# audio_spectrum.net
KiCad netlist of a schematic drawn in EAGLE
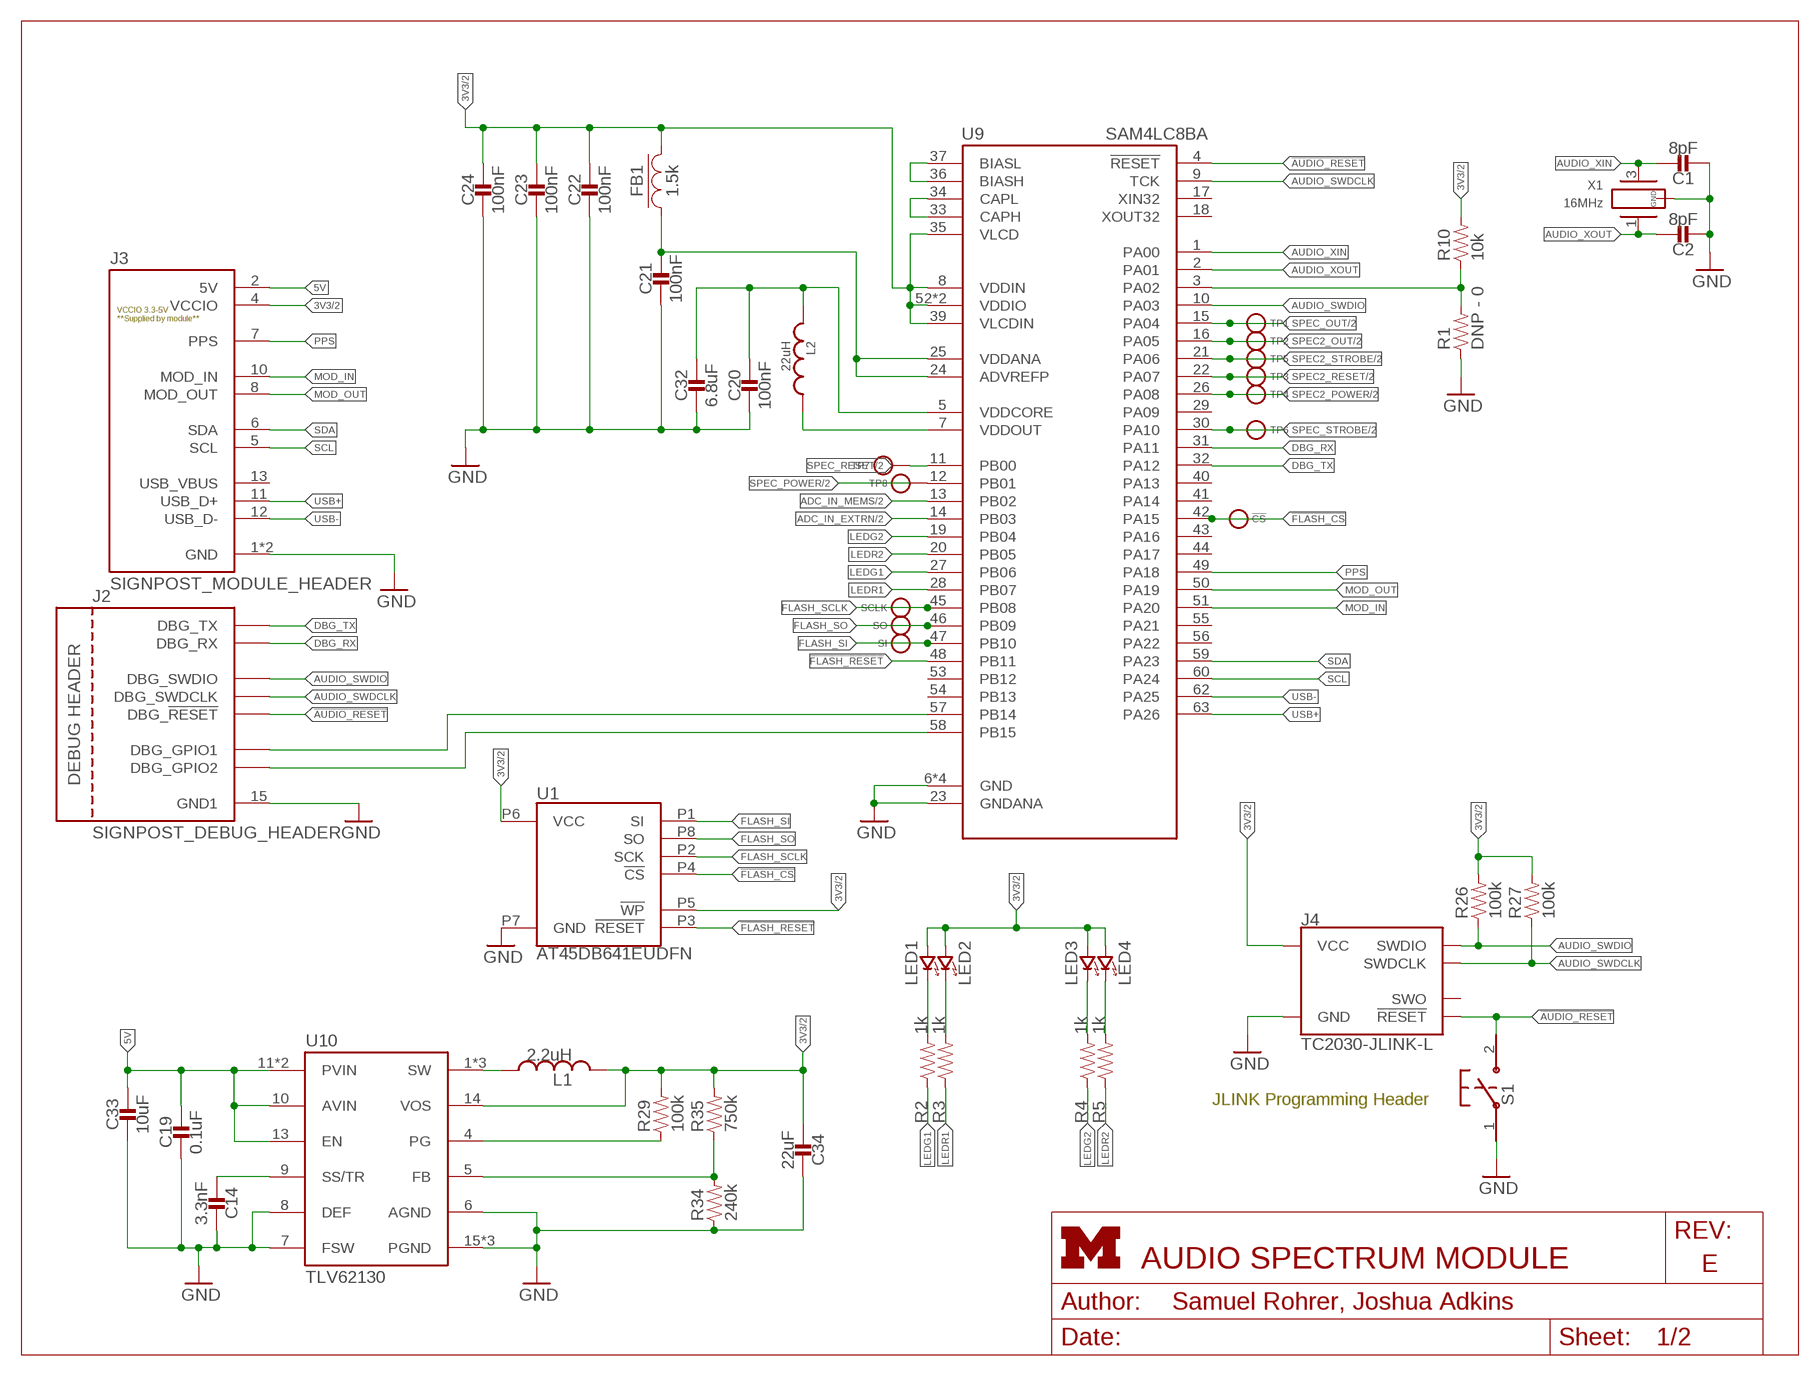
[diagram p0: schematic, sheet 1]
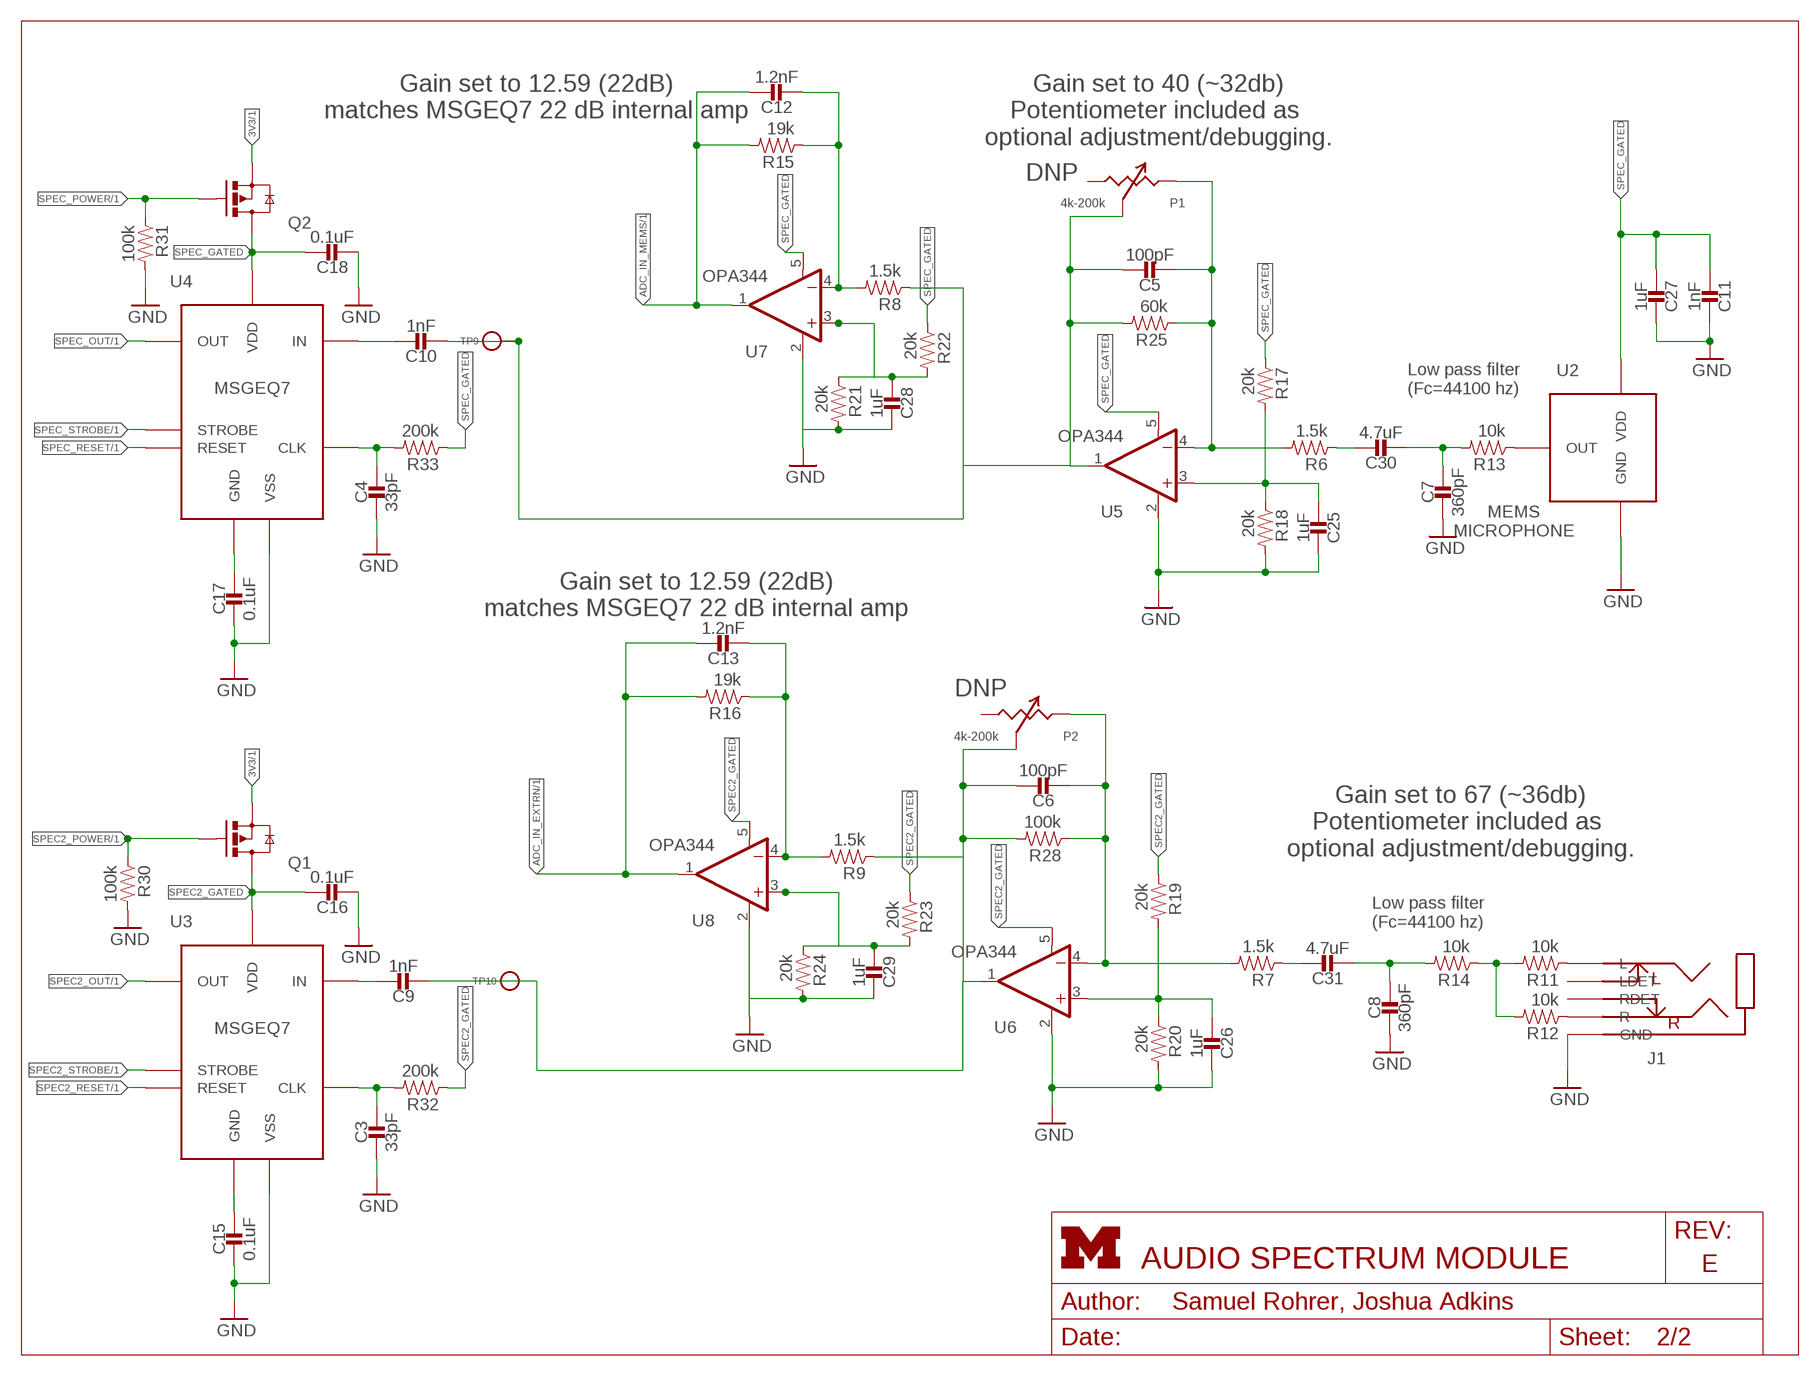
[diagram p1: schematic, sheet 2]

(export (version "E")
  (design (tool "Eeschema 10.0.6"))
  (components
    (comp (ref "!CS")
      (value "TEST_POINT_0.040IN")
      (footprint "eagle-import:TESTPOINT_0.040IN")
      (libsource (lib "eagle-import") (part "TEST_POINT_0.040IN"))
    )
    (comp (ref "C1")
      (value "8pF")
      (footprint "eagle-import:0402_CAP")
      (fields (field (name "MANUFACTURER") "Murata") (field (name "MPN") "GRM1555C1H8R0BA01D"))
      (libsource (lib "eagle-import") (part "CAPACITOR0402_CAP"))
    )
    (comp (ref "C2")
      (value "8pF")
      (footprint "eagle-import:0402_CAP")
      (fields (field (name "MANUFACTURER") "Murata") (field (name "MPN") "GRM1555C1H8R0BA01D"))
      (libsource (lib "eagle-import") (part "CAPACITOR0402_CAP"))
    )
    (comp (ref "C14")
      (value "3.3nF")
      (footprint "eagle-import:0603_CAP")
      (fields (field (name "MANUFACTURER") "Murata") (field (name "MPN") "GRM188R71H332KA01D"))
      (libsource (lib "eagle-import") (part "CAPACITOR0603_CAP"))
    )
    (comp (ref "C19")
      (value "0.1uF")
      (footprint "eagle-import:0603_CAP")
      (fields (field (name "MANUFACTURER") "Murata") (field (name "MPN") "GRM188R71C104KA01D"))
      (libsource (lib "eagle-import") (part "CAPACITOR0603_CAP"))
    )
    (comp (ref "C20")
      (value "100nF")
      (footprint "eagle-import:0402_CAP")
      (fields (field (name "MANUFACTURER") "Murata") (field (name "MPN") "GRM155R71A104JA01D"))
      (libsource (lib "eagle-import") (part "CAPACITOR0402_CAP"))
    )
    (comp (ref "C21")
      (value "100nF")
      (footprint "eagle-import:0603_CAP")
      (fields (field (name "MANUFACTURER") "Murata") (field (name "MPN") "GRM188R71C104KA01D"))
      (libsource (lib "eagle-import") (part "CAPACITOR0603_CAP"))
    )
    (comp (ref "C22")
      (value "100nF")
      (footprint "eagle-import:0603_CAP")
      (fields (field (name "MANUFACTURER") "Murata") (field (name "MPN") "GRM188R71C104KA01D"))
      (libsource (lib "eagle-import") (part "CAPACITOR0603_CAP"))
    )
    (comp (ref "C23")
      (value "100nF")
      (footprint "eagle-import:0603_CAP")
      (fields (field (name "MANUFACTURER") "Murata") (field (name "MPN") "GRM188R71C104KA01D"))
      (libsource (lib "eagle-import") (part "CAPACITOR0603_CAP"))
    )
    (comp (ref "C24")
      (value "100nF")
      (footprint "eagle-import:0603_CAP")
      (fields (field (name "MANUFACTURER") "Murata") (field (name "MPN") "GRM188R71C104KA01D"))
      (libsource (lib "eagle-import") (part "CAPACITOR0603_CAP"))
    )
    (comp (ref "C32")
      (value "6.8uF")
      (footprint "eagle-import:0603_CAP")
      (fields (field (name "MANUFACTURER") "TDk") (field (name "MPN") "C1608X5R1A685K080AC"))
      (libsource (lib "eagle-import") (part "CAPACITOR0603_CAP"))
    )
    (comp (ref "C33")
      (value "10uF")
      (footprint "eagle-import:0603_CAP")
      (fields (field (name "MANUFACTURER") "Murata") (field (name "MPN") "GRM188R60J106ME47J"))
      (libsource (lib "eagle-import") (part "CAPACITOR0603_CAP"))
    )
    (comp (ref "C34")
      (value "22uF")
      (footprint "eagle-import:0603_CAP")
      (fields (field (name "MANUFACTURER") "Murata") (field (name "MPN") "GRM186R60J226ME15D"))
      (libsource (lib "eagle-import") (part "CAPACITOR0603_CAP"))
    )
    (comp (ref "FB1")
      (value "1.5k")
      (footprint "eagle-import:0402_CAP")
      (fields (field (name "MANUFACTURER") "Murata") (field (name "MPN") "BLM18HE152SN1D"))
      (libsource (lib "eagle-import") (part "FERRITE_BEAD0402"))
    )
    (comp (ref "J2")
      (value "SIGNPOST_DEBUG_HEADER")
      (footprint "eagle-import:SIGNPOST_DEBUG_HEADER")
      (fields (field (name "MANUFACTURER") "Sullins Connector") (field (name "MPN") "PRPC004DFBN-RC"))
      (libsource (lib "eagle-import") (part "SIGNPOST_DEBUG_HEADER"))
    )
    (comp (ref "J3")
      (value "SIGNPOST_MODULE_HEADER")
      (footprint "eagle-import:SIGNPOST_MODULE_HEADER")
      (fields (field (name "MANUFACTURER") "Sullins Connector") (field (name "MPN") "SBH11-PBPC-D07-ST-BK"))
      (libsource (lib "eagle-import") (part "SIGNPOST_MODULE_HEADER"))
    )
    (comp (ref "J4")
      (value "TC2030-JLINK-L")
      (footprint "eagle-import:TC2030-IDC")
      (libsource (lib "eagle-import") (part "TC2030-JLINK-L"))
    )
    (comp (ref "L1")
      (value "2.2uH")
      (footprint "eagle-import:IHL-1212BZ-11")
      (fields (field (name "MANUFACTURER") "Vishay Dale") (field (name "MPN") "IHLP1212BZER2R2M11"))
      (libsource (lib "eagle-import") (part "INDUCTORIHL"))
    )
    (comp (ref "L2")
      (value "22uH")
      (footprint "eagle-import:1212")
      (fields
        (field (name "MANUFACTURER") "Murata")
        (field (name "MPN") "LQH3NPN220MJ0L")
        (field (name "MANUFACTURER_1") "Murata")
        (field (name "MPN_1") "LQH3NPN220MJ0L")
      )
      (libsource (lib "eagle-import") (part "LHQ3NP"))
    )
    (comp (ref "LED1")
      (value "LED0603")
      (footprint "eagle-import:LED-0603")
      (fields (field (name "MANUFACTURER") "Lite-On") (field (name "MPN") "LTST-C191KGKT"))
      (libsource (lib "eagle-import") (part "LED0603"))
    )
    (comp (ref "LED2")
      (value "LED0603")
      (footprint "eagle-import:LED-0603")
      (fields (field (name "MANUFACTURER") "Lite-On") (field (name "MPN") "LTST-C191KRKT"))
      (libsource (lib "eagle-import") (part "LED0603"))
    )
    (comp (ref "LED3")
      (value "LED0603")
      (footprint "eagle-import:LED-0603")
      (fields (field (name "MANUFACTURER") "Lite-On") (field (name "MPN") "LTST-C191KGKT"))
      (libsource (lib "eagle-import") (part "LED0603"))
    )
    (comp (ref "LED4")
      (value "LED0603")
      (footprint "eagle-import:LED-0603")
      (fields (field (name "MANUFACTURER") "Lite-On") (field (name "MPN") "LTST-C191KRKT"))
      (libsource (lib "eagle-import") (part "LED0603"))
    )
    (comp (ref "R1")
      (value "DNP - 0")
      (footprint "eagle-import:0603-RES")
      (fields (field (name "MANUFACTURER") "Samsung") (field (name "MPN") "RC1005F103CS"))
      (libsource (lib "eagle-import") (part "RESISTOR0603_RES"))
    )
    (comp (ref "R2")
      (value "1k")
      (footprint "eagle-import:0603-RES")
      (fields (field (name "MANUFACTURER") "Murata") (field (name "MPN") "ESR03EZPJ102"))
      (libsource (lib "eagle-import") (part "RESISTOR0603_RES"))
    )
    (comp (ref "R3")
      (value "1k")
      (footprint "eagle-import:0603-RES")
      (fields (field (name "MANUFACTURER") "Murata") (field (name "MPN") "ESR03EZPJ102"))
      (libsource (lib "eagle-import") (part "RESISTOR0603_RES"))
    )
    (comp (ref "R4")
      (value "1k")
      (footprint "eagle-import:0603-RES")
      (fields (field (name "MANUFACTURER") "Murata") (field (name "MPN") "ESR03EZPJ102"))
      (libsource (lib "eagle-import") (part "RESISTOR0603_RES"))
    )
    (comp (ref "R5")
      (value "1k")
      (footprint "eagle-import:0603-RES")
      (fields (field (name "MANUFACTURER") "Murata") (field (name "MPN") "ESR03EZPJ102"))
      (libsource (lib "eagle-import") (part "RESISTOR0603_RES"))
    )
    (comp (ref "R10")
      (value "10k")
      (footprint "eagle-import:0603-RES")
      (fields (field (name "MANUFACTURER") "Rohm") (field (name "MPN") "MCR03EZPFX1002"))
      (libsource (lib "eagle-import") (part "RESISTOR0603_RES"))
    )
    (comp (ref "R26")
      (value "100k")
      (footprint "eagle-import:0603-RES")
      (fields (field (name "MANUFACTURER") "Rohm") (field (name "MPN") "MCR03ERTJ104"))
      (libsource (lib "eagle-import") (part "RESISTOR0603_RES"))
    )
    (comp (ref "R27")
      (value "100k")
      (footprint "eagle-import:0603-RES")
      (fields (field (name "MANUFACTURER") "Rohm") (field (name "MPN") "MCR03ERTJ104"))
      (libsource (lib "eagle-import") (part "RESISTOR0603_RES"))
    )
    (comp (ref "R29")
      (value "100k")
      (footprint "eagle-import:0603-RES")
      (fields (field (name "MANUFACTURER") "Rohm") (field (name "MPN") "MCR03ERTJ104"))
      (libsource (lib "eagle-import") (part "RESISTOR0603_RES"))
    )
    (comp (ref "R34")
      (value "240k")
      (footprint "eagle-import:0603-RES")
      (fields (field (name "MANUFACTURER") "Rohm") (field (name "MPN") "RHM240KCFCT-ND"))
      (libsource (lib "eagle-import") (part "RESISTOR0603_RES"))
    )
    (comp (ref "R35")
      (value "750k")
      (footprint "eagle-import:0603-RES")
      (fields (field (name "MANUFACTURER") "Rohm") (field (name "MPN") "MCR03ERTF7503"))
      (libsource (lib "eagle-import") (part "RESISTOR0603_RES"))
    )
    (comp (ref "S1")
      (value "B3U-1000P")
      (footprint "eagle-import:B3U-1000P")
      (fields (field (name "MANUFACTURER") "Omron"))
      (libsource (lib "eagle-import") (part "B3U-1000P"))
    )
    (comp (ref "SCLK")
      (value "TEST_POINT_0.040IN")
      (footprint "eagle-import:TESTPOINT_0.040IN")
      (libsource (lib "eagle-import") (part "TEST_POINT_0.040IN"))
    )
    (comp (ref "SI")
      (value "TEST_POINT_0.040IN")
      (footprint "eagle-import:TESTPOINT_0.040IN")
      (libsource (lib "eagle-import") (part "TEST_POINT_0.040IN"))
    )
    (comp (ref "SO")
      (value "TEST_POINT_0.040IN")
      (footprint "eagle-import:TESTPOINT_0.040IN")
      (libsource (lib "eagle-import") (part "TEST_POINT_0.040IN"))
    )
    (comp (ref "TP1")
      (value "TEST_POINT_0.040IN")
      (footprint "eagle-import:TESTPOINT_0.040IN")
      (libsource (lib "eagle-import") (part "TEST_POINT_0.040IN"))
    )
    (comp (ref "TP2")
      (value "TEST_POINT_0.040IN")
      (footprint "eagle-import:TESTPOINT_0.040IN")
      (libsource (lib "eagle-import") (part "TEST_POINT_0.040IN"))
    )
    (comp (ref "TP3")
      (value "TEST_POINT_0.040IN")
      (footprint "eagle-import:TESTPOINT_0.040IN")
      (libsource (lib "eagle-import") (part "TEST_POINT_0.040IN"))
    )
    (comp (ref "TP4")
      (value "TEST_POINT_0.040IN")
      (footprint "eagle-import:TESTPOINT_0.040IN")
      (libsource (lib "eagle-import") (part "TEST_POINT_0.040IN"))
    )
    (comp (ref "TP5")
      (value "TEST_POINT_0.040IN")
      (footprint "eagle-import:TESTPOINT_0.040IN")
      (libsource (lib "eagle-import") (part "TEST_POINT_0.040IN"))
    )
    (comp (ref "TP6")
      (value "TEST_POINT_0.040IN")
      (footprint "eagle-import:TESTPOINT_0.040IN")
      (libsource (lib "eagle-import") (part "TEST_POINT_0.040IN"))
    )
    (comp (ref "TP7")
      (value "TEST_POINT_0.040IN")
      (footprint "eagle-import:TESTPOINT_0.040IN")
      (libsource (lib "eagle-import") (part "TEST_POINT_0.040IN"))
    )
    (comp (ref "TP8")
      (value "TEST_POINT_0.040IN")
      (footprint "eagle-import:TESTPOINT_0.040IN")
      (libsource (lib "eagle-import") (part "TEST_POINT_0.040IN"))
    )
    (comp (ref "U1")
      (value "AT45DB641EUDFN")
      (footprint "eagle-import:UDFN-8-5MMX6MM")
      (fields (field (name "MANUFACTURER") "Adesto") (field (name "MPN") "AT45DB641E-MHN-T"))
      (libsource (lib "eagle-import") (part "AT45DB641EUDFN"))
    )
    (comp (ref "U9")
      (value "SAM4LC8BA")
      (footprint "eagle-import:QFN-64-9MM")
      (fields (field (name "MANUFACTURER") "Microchip") (field (name "MPN") "ATSAM4LC8BA-MUR"))
      (libsource (lib "eagle-import") (part "SAM4LC8BA"))
    )
    (comp (ref "U10")
      (value "TLV62130")
      (footprint "eagle-import:TQFN-16_3MM")
      (fields (field (name "MANUFACTURER") "Texas Instruments") (field (name "MPN") "TLV62130RGTR"))
      (libsource (lib "eagle-import") (part "TLV62130"))
    )
    (comp (ref "X1")
      (value "16MHz")
      (footprint "eagle-import:FHXXX")
      (fields (field (name "MANUFACTURER") "Diodes Incorporated") (field (name "MPN") "FH1600015"))
      (libsource (lib "eagle-import") (part "FH1600015"))
    )
    (comp (ref "C3")
      (value "33pF")
      (footprint "eagle-import:0603_CAP")
      (fields (field (name "MANUFACTURER") "Murata") (field (name "MPN") "GRM1885C1H330JA01D"))
      (libsource (lib "eagle-import") (part "CAPACITOR0603_CAP"))
    )
    (comp (ref "C4")
      (value "33pF")
      (footprint "eagle-import:0603_CAP")
      (fields (field (name "MANUFACTURER") "Murata") (field (name "MPN") "GRM1885C1H330JA01D"))
      (libsource (lib "eagle-import") (part "CAPACITOR0603_CAP"))
    )
    (comp (ref "C5")
      (value "100pF")
      (footprint "eagle-import:0603_CAP")
      (fields (field (name "MANUFACTURER") "Murata") (field (name "MPN") "GRM1885C1H101JA01D"))
      (libsource (lib "eagle-import") (part "CAPACITOR0603_CAP"))
    )
    (comp (ref "C6")
      (value "100pF")
      (footprint "eagle-import:0603_CAP")
      (fields (field (name "MANUFACTURER") "Murata") (field (name "MPN") "GRM1885C1H101JA01D"))
      (libsource (lib "eagle-import") (part "CAPACITOR0603_CAP"))
    )
    (comp (ref "C7")
      (value "360pF")
      (footprint "eagle-import:0603_CAP")
      (fields (field (name "MANUFACTURER") "Murata") (field (name "MPN") "GRM1885C1H361JA01D"))
      (libsource (lib "eagle-import") (part "CAPACITOR0603_CAP"))
    )
    (comp (ref "C8")
      (value "360pF")
      (footprint "eagle-import:0603_CAP")
      (fields (field (name "MANUFACTURER") "Murata") (field (name "MPN") "GRM1885C1H361JA01D"))
      (libsource (lib "eagle-import") (part "CAPACITOR0603_CAP"))
    )
    (comp (ref "C9")
      (value "1nF")
      (footprint "eagle-import:0603_CAP")
      (fields (field (name "MANUFACTURER") "Murata") (field (name "MPN") "GRM188R71H102KA01D"))
      (libsource (lib "eagle-import") (part "CAPACITOR0603_CAP"))
    )
    (comp (ref "C10")
      (value "1nF")
      (footprint "eagle-import:0603_CAP")
      (fields (field (name "MANUFACTURER") "Murata") (field (name "MPN") "GRM188R71H102KA01D"))
      (libsource (lib "eagle-import") (part "CAPACITOR0603_CAP"))
    )
    (comp (ref "C11")
      (value "1nF")
      (footprint "eagle-import:0603_CAP")
      (fields (field (name "MANUFACTURER") "Murata") (field (name "MPN") "GRM188R71H102KA01D"))
      (libsource (lib "eagle-import") (part "CAPACITOR0603_CAP"))
    )
    (comp (ref "C12")
      (value "1.2nF")
      (footprint "eagle-import:0603_CAP")
      (fields (field (name "MANUFACTURER") "Murata") (field (name "MPN") "GCM1885C1H122JA16D"))
      (libsource (lib "eagle-import") (part "CAPACITOR0603_CAP"))
    )
    (comp (ref "C13")
      (value "1.2nF")
      (footprint "eagle-import:0603_CAP")
      (fields (field (name "MANUFACTURER") "Murata") (field (name "MPN") "GCM1885C1H122JA16D"))
      (libsource (lib "eagle-import") (part "CAPACITOR0603_CAP"))
    )
    (comp (ref "C15")
      (value "0.1uF")
      (footprint "eagle-import:0603_CAP")
      (fields (field (name "MANUFACTURER") "Murata") (field (name "MPN") "GRM188R71C104KA01D"))
      (libsource (lib "eagle-import") (part "CAPACITOR0603_CAP"))
    )
    (comp (ref "C16")
      (value "0.1uF")
      (footprint "eagle-import:0603_CAP")
      (fields (field (name "MANUFACTURER") "Murata") (field (name "MPN") "GRM188R71C104KA01D"))
      (libsource (lib "eagle-import") (part "CAPACITOR0603_CAP"))
    )
    (comp (ref "C17")
      (value "0.1uF")
      (footprint "eagle-import:0603_CAP")
      (fields (field (name "MANUFACTURER") "Murata") (field (name "MPN") "GRM188R71C104KA01D"))
      (libsource (lib "eagle-import") (part "CAPACITOR0603_CAP"))
    )
    (comp (ref "C18")
      (value "0.1uF")
      (footprint "eagle-import:0603_CAP")
      (fields (field (name "MANUFACTURER") "Murata") (field (name "MPN") "GRM188R71C104KA01D"))
      (libsource (lib "eagle-import") (part "CAPACITOR0603_CAP"))
    )
    (comp (ref "C25")
      (value "1uF")
      (footprint "eagle-import:0603_CAP")
      (fields (field (name "MANUFACTURER") "Murata") (field (name "MPN") "GRM188R61C105KA93D"))
      (libsource (lib "eagle-import") (part "CAPACITOR0603_CAP"))
    )
    (comp (ref "C26")
      (value "1uF")
      (footprint "eagle-import:0603_CAP")
      (fields (field (name "MANUFACTURER") "Murata") (field (name "MPN") "GRM188R61C105KA93D"))
      (libsource (lib "eagle-import") (part "CAPACITOR0603_CAP"))
    )
    (comp (ref "C27")
      (value "1uF")
      (footprint "eagle-import:0603_CAP")
      (fields (field (name "MANUFACTURER") "Murata") (field (name "MPN") "GRM188R61C105KA93D"))
      (libsource (lib "eagle-import") (part "CAPACITOR0603_CAP"))
    )
    (comp (ref "C28")
      (value "1uF")
      (footprint "eagle-import:0603_CAP")
      (fields (field (name "MANUFACTURER") "Murata") (field (name "MPN") "GRM188R61C105KA93D"))
      (libsource (lib "eagle-import") (part "CAPACITOR0603_CAP"))
    )
    (comp (ref "C29")
      (value "1uF")
      (footprint "eagle-import:0603_CAP")
      (fields (field (name "MANUFACTURER") "Murata") (field (name "MPN") "GRM188R61C105KA93D"))
      (libsource (lib "eagle-import") (part "CAPACITOR0603_CAP"))
    )
    (comp (ref "C30")
      (value "4.7uF")
      (footprint "eagle-import:0603_CAP")
      (fields (field (name "MANUFACTURER") "Murata") (field (name "MPN") "GRM188R60J475KE19D"))
      (libsource (lib "eagle-import") (part "CAPACITOR0603_CAP"))
    )
    (comp (ref "C31")
      (value "4.7uF")
      (footprint "eagle-import:0603_CAP")
      (fields (field (name "MANUFACTURER") "Murata") (field (name "MPN") "GRM188R60J475KE19D"))
      (libsource (lib "eagle-import") (part "CAPACITOR0603_CAP"))
    )
    (comp (ref "J1")
      (value "AUDIO-JACK-VERTICAL")
      (footprint "eagle-import:AUDIO-JACK-VERTICAL")
      (fields
        (field (name "MANUFACTURER") "Kycon")
        (field (name "MPN") "STX-3790-5N")
        (field (name "MANUFACTURER_1") "Kycon")
        (field (name "MPN_1") "STX-3790-5N")
      )
      (libsource (lib "eagle-import") (part "AUDIO-JACK-VERTICAL"))
    )
    (comp (ref "P1")
      (value "4k-200k")
      (footprint "eagle-import:TC33X-2")
      (libsource (lib "eagle-import") (part "POTTC33X"))
    )
    (comp (ref "P2")
      (value "4k-200k")
      (footprint "eagle-import:TC33X-2")
      (libsource (lib "eagle-import") (part "POTTC33X"))
    )
    (comp (ref "Q1")
      (value "NX3008PBK")
      (footprint "eagle-import:SOT23-3")
      (fields (field (name "MANUFACTURER") "Nexperia") (field (name "MPN") "NX3008PBK,215"))
      (libsource (lib "eagle-import") (part "NX3008PBK"))
    )
    (comp (ref "Q2")
      (value "NX3008PBK")
      (footprint "eagle-import:SOT23-3")
      (fields (field (name "MANUFACTURER") "Nexperia") (field (name "MPN") "NX3008PBK,215"))
      (libsource (lib "eagle-import") (part "NX3008PBK"))
    )
    (comp (ref "R6")
      (value "1.5k")
      (footprint "eagle-import:0603-RES")
      (fields (field (name "MANUFACTURER") "Rohm") (field (name "MPN") "MCR03ERTJ152 "))
      (libsource (lib "eagle-import") (part "RESISTOR0603_RES"))
    )
    (comp (ref "R7")
      (value "1.5k")
      (footprint "eagle-import:0603-RES")
      (fields (field (name "MANUFACTURER") "Rohm") (field (name "MPN") "MCR03ERTJ152 "))
      (libsource (lib "eagle-import") (part "RESISTOR0603_RES"))
    )
    (comp (ref "R8")
      (value "1.5k")
      (footprint "eagle-import:0603-RES")
      (fields (field (name "MANUFACTURER") "Rohm") (field (name "MPN") "MCR03ERTJ152"))
      (libsource (lib "eagle-import") (part "RESISTOR0603_RES"))
    )
    (comp (ref "R9")
      (value "1.5k")
      (footprint "eagle-import:0603-RES")
      (fields (field (name "MANUFACTURER") "Rohm") (field (name "MPN") "MCR03ERTJ152"))
      (libsource (lib "eagle-import") (part "RESISTOR0603_RES"))
    )
    (comp (ref "R11")
      (value "10k")
      (footprint "eagle-import:0603-RES")
      (fields (field (name "MANUFACTURER") "Rohm") (field (name "MPN") "MCR03EZPFX1002"))
      (libsource (lib "eagle-import") (part "RESISTOR0603_RES"))
    )
    (comp (ref "R12")
      (value "10k")
      (footprint "eagle-import:0603-RES")
      (fields (field (name "MANUFACTURER") "Rohm") (field (name "MPN") "MCR03EZPFX1002"))
      (libsource (lib "eagle-import") (part "RESISTOR0603_RES"))
    )
    (comp (ref "R13")
      (value "10k")
      (footprint "eagle-import:0603-RES")
      (fields (field (name "MANUFACTURER") "Rohm") (field (name "MPN") "MCR03EZPFX1002"))
      (libsource (lib "eagle-import") (part "RESISTOR0603_RES"))
    )
    (comp (ref "R14")
      (value "10k")
      (footprint "eagle-import:0603-RES")
      (fields (field (name "MANUFACTURER") "Rohm") (field (name "MPN") "MCR03EZPFX1002"))
      (libsource (lib "eagle-import") (part "RESISTOR0603_RES"))
    )
    (comp (ref "R15")
      (value "19k")
      (footprint "eagle-import:0603-RES")
      (fields (field (name "MANUFACTURER") "Rohm") (field (name "MPN") "MCR03ERTF1912"))
      (libsource (lib "eagle-import") (part "RESISTOR0603_RES"))
    )
    (comp (ref "R16")
      (value "19k")
      (footprint "eagle-import:0603-RES")
      (fields (field (name "MANUFACTURER") "Rohm") (field (name "MPN") "MCR03ERTF1912"))
      (libsource (lib "eagle-import") (part "RESISTOR0603_RES"))
    )
    (comp (ref "R17")
      (value "20k")
      (footprint "eagle-import:0603-RES")
      (fields (field (name "MANUFACTURER") "Rohm") (field (name "MPN") "MCR03ERTJ203"))
      (libsource (lib "eagle-import") (part "RESISTOR0603_RES"))
    )
    (comp (ref "R18")
      (value "20k")
      (footprint "eagle-import:0603-RES")
      (fields (field (name "MANUFACTURER") "Rohm") (field (name "MPN") "MCR03ERTJ203"))
      (libsource (lib "eagle-import") (part "RESISTOR0603_RES"))
    )
    (comp (ref "R19")
      (value "20k")
      (footprint "eagle-import:0603-RES")
      (fields (field (name "MANUFACTURER") "Rohm") (field (name "MPN") "MCR03ERTJ203"))
      (libsource (lib "eagle-import") (part "RESISTOR0603_RES"))
    )
    (comp (ref "R20")
      (value "20k")
      (footprint "eagle-import:0603-RES")
      (fields (field (name "MANUFACTURER") "Rohm") (field (name "MPN") "MCR03ERTJ203"))
      (libsource (lib "eagle-import") (part "RESISTOR0603_RES"))
    )
    (comp (ref "R21")
      (value "20k")
      (footprint "eagle-import:0603-RES")
      (fields (field (name "MANUFACTURER") "Rohm") (field (name "MPN") "MCR03ERTJ203"))
      (libsource (lib "eagle-import") (part "RESISTOR0603_RES"))
    )
    (comp (ref "R22")
      (value "20k")
      (footprint "eagle-import:0603-RES")
      (fields (field (name "MANUFACTURER") "Rohm") (field (name "MPN") "MCR03ERTJ203"))
      (libsource (lib "eagle-import") (part "RESISTOR0603_RES"))
    )
    (comp (ref "R23")
      (value "20k")
      (footprint "eagle-import:0603-RES")
      (fields (field (name "MANUFACTURER") "Rohm") (field (name "MPN") "MCR03ERTJ203"))
      (libsource (lib "eagle-import") (part "RESISTOR0603_RES"))
    )
    (comp (ref "R24")
      (value "20k")
      (footprint "eagle-import:0603-RES")
      (fields (field (name "MANUFACTURER") "Rohm") (field (name "MPN") "MCR03ERTJ203"))
      (libsource (lib "eagle-import") (part "RESISTOR0603_RES"))
    )
    (comp (ref "R25")
      (value "60k")
      (footprint "eagle-import:0603-RES")
      (fields (field (name "MANUFACTURER") "Rohm") (field (name "MPN") "MCR03ERTF6042"))
      (libsource (lib "eagle-import") (part "RESISTOR0603_RES"))
    )
    (comp (ref "R28")
      (value "100k")
      (footprint "eagle-import:0603-RES")
      (fields (field (name "MANUFACTURER") "Rohm") (field (name "MPN") "MCR03ERTJ104"))
      (libsource (lib "eagle-import") (part "RESISTOR0603_RES"))
    )
    (comp (ref "R30")
      (value "100k")
      (footprint "eagle-import:0603-RES")
      (fields (field (name "MANUFACTURER") "Rohm") (field (name "MPN") "MCR03ERTJ104"))
      (libsource (lib "eagle-import") (part "RESISTOR0603_RES"))
    )
    (comp (ref "R31")
      (value "100k")
      (footprint "eagle-import:0603-RES")
      (fields (field (name "MANUFACTURER") "Rohm") (field (name "MPN") "MCR03ERTJ104"))
      (libsource (lib "eagle-import") (part "RESISTOR0603_RES"))
    )
    (comp (ref "R32")
      (value "200k")
      (footprint "eagle-import:0603-RES")
      (fields (field (name "MANUFACTURER") "Rohm") (field (name "MPN") "MCR03ERTF2003"))
      (libsource (lib "eagle-import") (part "RESISTOR0603_RES"))
    )
    (comp (ref "R33")
      (value "200k")
      (footprint "eagle-import:0603-RES")
      (fields (field (name "MANUFACTURER") "Rohm") (field (name "MPN") "MCR03ERTF2003"))
      (libsource (lib "eagle-import") (part "RESISTOR0603_RES"))
    )
    (comp (ref "TP9")
      (value "TEST_POINT_0.040IN")
      (footprint "eagle-import:TESTPOINT_0.040IN")
      (libsource (lib "eagle-import") (part "TEST_POINT_0.040IN"))
    )
    (comp (ref "TP10")
      (value "TEST_POINT_0.040IN")
      (footprint "eagle-import:TESTPOINT_0.040IN")
      (libsource (lib "eagle-import") (part "TEST_POINT_0.040IN"))
    )
    (comp (ref "U2")
      (value "MP23AB02B")
      (footprint "eagle-import:MP23AB02B")
      (fields (field (name "MANUFACTURER") "STMicroelectronics") (field (name "MPN") "MP23AB02BTR"))
      (libsource (lib "eagle-import") (part "MP23AB02B"))
    )
    (comp (ref "U3")
      (value "MSGEQ7")
      (footprint "eagle-import:DIP-8")
      (fields (field (name "MANUFACTURER") "Sparkfun Electronics") (field (name "MPN") "COM-10468"))
      (libsource (lib "eagle-import") (part "MSGEQ7"))
    )
    (comp (ref "U4")
      (value "MSGEQ7")
      (footprint "eagle-import:DIP-8")
      (fields (field (name "MANUFACTURER") "Sparkfun Electronics") (field (name "MPN") "COM-10468"))
      (libsource (lib "eagle-import") (part "MSGEQ7"))
    )
    (comp (ref "U5")
      (value "OPA344")
      (footprint "eagle-import:SOT23-5")
      (fields
        (field (name "MANUFACTURER") "Texax Instruments")
        (field (name "MPN") "OPA344NA/250")
        (field (name "DIGIKEY") "OPA344NACT-ND")
      )
      (libsource (lib "eagle-import") (part "OPA344"))
    )
    (comp (ref "U6")
      (value "OPA344")
      (footprint "eagle-import:SOT23-5")
      (fields
        (field (name "MANUFACTURER") "Texax Instruments")
        (field (name "MPN") "OPA344NA/250")
        (field (name "DIGIKEY") "OPA344NACT-ND")
      )
      (libsource (lib "eagle-import") (part "OPA344"))
    )
    (comp (ref "U7")
      (value "OPA344")
      (footprint "eagle-import:SOT23-5")
      (fields
        (field (name "MANUFACTURER") "Texax Instruments")
        (field (name "MPN") "OPA344NA/250")
        (field (name "DIGIKEY") "OPA344NACT-ND")
      )
      (libsource (lib "eagle-import") (part "OPA344"))
    )
    (comp (ref "U8")
      (value "OPA344")
      (footprint "eagle-import:SOT23-5")
      (fields
        (field (name "MANUFACTURER") "Texax Instruments")
        (field (name "MPN") "OPA344NA/250")
        (field (name "DIGIKEY") "OPA344NACT-ND")
      )
      (libsource (lib "eagle-import") (part "OPA344"))
    )
  )
  (nets
    (net (code "1") (name "3V3") (class "Default")
      (node (ref "C22") (pin "1") (pinfunction "1_1") (pintype "bidirectional"))
      (node (ref "C23") (pin "1") (pinfunction "1_1") (pintype "bidirectional"))
      (node (ref "C24") (pin "1") (pinfunction "1_1") (pintype "bidirectional"))
      (node (ref "C34") (pin "2") (pinfunction "2_2") (pintype "bidirectional"))
      (node (ref "FB1") (pin "2") (pinfunction "P$2_2") (pintype "bidirectional"))
      (node (ref "J3") (pin "4") (pinfunction "VCCIO_4") (pintype "bidirectional"))
      (node (ref "J4") (pin "1") (pinfunction "VCC_1") (pintype "bidirectional"))
      (node (ref "L1") (pin "P$2") (pinfunction "2_P$2") (pintype "bidirectional"))
      (node (ref "LED1") (pin "A") (pinfunction "ANODE_A") (pintype "bidirectional"))
      (node (ref "LED2") (pin "A") (pinfunction "ANODE_A") (pintype "bidirectional"))
      (node (ref "LED3") (pin "A") (pinfunction "ANODE_A") (pintype "bidirectional"))
      (node (ref "LED4") (pin "A") (pinfunction "ANODE_A") (pintype "bidirectional"))
      (node (ref "Q1") (pin "2") (pinfunction "S_2") (pintype "passive"))
      (node (ref "Q2") (pin "2") (pinfunction "S_2") (pintype "passive"))
      (node (ref "R10") (pin "2") (pinfunction "2_2") (pintype "passive"))
      (node (ref "R26") (pin "2") (pinfunction "2_2") (pintype "passive"))
      (node (ref "R27") (pin "2") (pinfunction "2_2") (pintype "passive"))
      (node (ref "R29") (pin "2") (pinfunction "2_2") (pintype "passive"))
      (node (ref "R35") (pin "2") (pinfunction "2_2") (pintype "passive"))
      (node (ref "U1") (pin "P5") (pinfunction "~{WP}_P5") (pintype "bidirectional"))
      (node (ref "U1") (pin "P6") (pinfunction "VCC_P6") (pintype "bidirectional"))
      (node (ref "U10") (pin "14") (pinfunction "VOS_14") (pintype "bidirectional"))
      (node (ref "U9") (pin "35") (pinfunction "VLCD_35") (pintype "bidirectional"))
      (node (ref "U9") (pin "39") (pinfunction "VLCDIN_39") (pintype "power_in"))
      (node (ref "U9") (pin "52") (pinfunction "VDDIO_52") (pintype "power_in"))
      (node (ref "U9") (pin "61") (pinfunction "VDDIO_61") (pintype "power_in"))
      (node (ref "U9") (pin "8") (pinfunction "VDDIN_8") (pintype "power_in"))
    )
    (net (code "2") (name "5V") (class "Default")
      (node (ref "C19") (pin "1") (pinfunction "1_1") (pintype "bidirectional"))
      (node (ref "C33") (pin "1") (pinfunction "1_1") (pintype "bidirectional"))
      (node (ref "J3") (pin "2") (pinfunction "5V_2") (pintype "bidirectional"))
      (node (ref "U10") (pin "10") (pinfunction "AVIN_10") (pintype "bidirectional"))
      (node (ref "U10") (pin "11") (pinfunction "PVIN_11") (pintype "bidirectional"))
      (node (ref "U10") (pin "12") (pinfunction "PVIN_12") (pintype "bidirectional"))
      (node (ref "U10") (pin "13") (pinfunction "EN_13") (pintype "bidirectional"))
    )
    (net (code "3") (name "ADC_IN_EXTRN") (class "Default")
      (node (ref "C13") (pin "1") (pinfunction "1_1") (pintype "bidirectional"))
      (node (ref "R16") (pin "2") (pinfunction "2_2") (pintype "passive"))
      (node (ref "U8") (pin "1") (pinfunction "OUT_1") (pintype "output"))
      (node (ref "U9") (pin "14") (pinfunction "PB03_14") (pintype "bidirectional"))
    )
    (net (code "4") (name "ADC_IN_MEMS") (class "Default")
      (node (ref "C12") (pin "1") (pinfunction "1_1") (pintype "bidirectional"))
      (node (ref "R15") (pin "2") (pinfunction "2_2") (pintype "passive"))
      (node (ref "U7") (pin "1") (pinfunction "OUT_1") (pintype "output"))
      (node (ref "U9") (pin "13") (pinfunction "PB02_13") (pintype "bidirectional"))
    )
    (net (code "5") (name "AUDIO_SWDCLK") (class "Default")
      (node (ref "J2") (pin "21") (pinfunction "DBG_SWDCLK_21") (pintype "bidirectional"))
      (node (ref "J4") (pin "4") (pinfunction "SWDCLK_4") (pintype "bidirectional"))
      (node (ref "R27") (pin "1") (pinfunction "1_1") (pintype "passive"))
      (node (ref "U9") (pin "9") (pinfunction "TCK_9") (pintype "bidirectional"))
    )
    (net (code "6") (name "AUDIO_SWDIO") (class "Default")
      (node (ref "J2") (pin "22") (pinfunction "DBG_SWDIO_22") (pintype "bidirectional"))
      (node (ref "J4") (pin "2") (pinfunction "SWDIO_2") (pintype "bidirectional"))
      (node (ref "R26") (pin "1") (pinfunction "1_1") (pintype "passive"))
      (node (ref "U9") (pin "10") (pinfunction "PA03_10") (pintype "bidirectional"))
    )
    (net (code "7") (name "AUDIO_XIN") (class "Default")
      (node (ref "C1") (pin "1") (pinfunction "1_1") (pintype "bidirectional"))
      (node (ref "U9") (pin "1") (pinfunction "PA00_1") (pintype "bidirectional"))
      (node (ref "X1") (pin "3") (pinfunction "2_3") (pintype "bidirectional"))
    )
    (net (code "8") (name "AUDIO_XOUT") (class "Default")
      (node (ref "C2") (pin "1") (pinfunction "1_1") (pintype "bidirectional"))
      (node (ref "U9") (pin "2") (pinfunction "PA01_2") (pintype "bidirectional"))
      (node (ref "X1") (pin "1") (pinfunction "1_1") (pintype "bidirectional"))
    )
    (net (code "9") (name "DBG_RX") (class "Default")
      (node (ref "J2") (pin "18") (pinfunction "DBG_RX_18") (pintype "bidirectional"))
      (node (ref "U9") (pin "31") (pinfunction "PA11_31") (pintype "bidirectional"))
    )
    (net (code "10") (name "DBG_TX") (class "Default")
      (node (ref "J2") (pin "17") (pinfunction "DBG_TX_17") (pintype "bidirectional"))
      (node (ref "U9") (pin "32") (pinfunction "PA12_32") (pintype "bidirectional"))
    )
    (net (code "11") (name "FLASH_SCLK") (class "Default")
      (node (ref "SCLK") (pin "TESTPOINT") (pinfunction "TESTPOINT_TESTPOINT") (pintype "bidirectional"))
      (node (ref "U1") (pin "P2") (pinfunction "SCK_P2") (pintype "bidirectional"))
      (node (ref "U9") (pin "45") (pinfunction "PB08_45") (pintype "bidirectional"))
    )
    (net (code "12") (name "FLASH_SI") (class "Default")
      (node (ref "SI") (pin "TESTPOINT") (pinfunction "TESTPOINT_TESTPOINT") (pintype "bidirectional"))
      (node (ref "U1") (pin "P1") (pinfunction "SI_P1") (pintype "bidirectional"))
      (node (ref "U9") (pin "47") (pinfunction "PB10_47") (pintype "bidirectional"))
    )
    (net (code "13") (name "FLASH_SO") (class "Default")
      (node (ref "SO") (pin "TESTPOINT") (pinfunction "TESTPOINT_TESTPOINT") (pintype "bidirectional"))
      (node (ref "U1") (pin "P8") (pinfunction "SO_P8") (pintype "bidirectional"))
      (node (ref "U9") (pin "46") (pinfunction "PB09_46") (pintype "bidirectional"))
    )
    (net (code "14") (name "GND") (class "Default")
      (node (ref "C1") (pin "2") (pinfunction "2_2") (pintype "bidirectional"))
      (node (ref "C11") (pin "1") (pinfunction "1_1") (pintype "bidirectional"))
      (node (ref "C14") (pin "1") (pinfunction "1_1") (pintype "bidirectional"))
      (node (ref "C15") (pin "2") (pinfunction "2_2") (pintype "bidirectional"))
      (node (ref "C16") (pin "2") (pinfunction "2_2") (pintype "bidirectional"))
      (node (ref "C17") (pin "2") (pinfunction "2_2") (pintype "bidirectional"))
      (node (ref "C18") (pin "2") (pinfunction "2_2") (pintype "bidirectional"))
      (node (ref "C19") (pin "2") (pinfunction "2_2") (pintype "bidirectional"))
      (node (ref "C2") (pin "2") (pinfunction "2_2") (pintype "bidirectional"))
      (node (ref "C20") (pin "2") (pinfunction "2_2") (pintype "bidirectional"))
      (node (ref "C21") (pin "2") (pinfunction "2_2") (pintype "bidirectional"))
      (node (ref "C22") (pin "2") (pinfunction "2_2") (pintype "bidirectional"))
      (node (ref "C23") (pin "2") (pinfunction "2_2") (pintype "bidirectional"))
      (node (ref "C24") (pin "2") (pinfunction "2_2") (pintype "bidirectional"))
      (node (ref "C25") (pin "1") (pinfunction "1_1") (pintype "bidirectional"))
      (node (ref "C26") (pin "1") (pinfunction "1_1") (pintype "bidirectional"))
      (node (ref "C27") (pin "1") (pinfunction "1_1") (pintype "bidirectional"))
      (node (ref "C28") (pin "1") (pinfunction "1_1") (pintype "bidirectional"))
      (node (ref "C29") (pin "1") (pinfunction "1_1") (pintype "bidirectional"))
      (node (ref "C3") (pin "2") (pinfunction "2_2") (pintype "bidirectional"))
      (node (ref "C32") (pin "2") (pinfunction "2_2") (pintype "bidirectional"))
      (node (ref "C33") (pin "2") (pinfunction "2_2") (pintype "bidirectional"))
      (node (ref "C34") (pin "1") (pinfunction "1_1") (pintype "bidirectional"))
      (node (ref "C4") (pin "2") (pinfunction "2_2") (pintype "bidirectional"))
      (node (ref "C7") (pin "2") (pinfunction "2_2") (pintype "bidirectional"))
      (node (ref "C8") (pin "2") (pinfunction "2_2") (pintype "bidirectional"))
      (node (ref "J1") (pin "5") (pinfunction "GND_5") (pintype "bidirectional"))
      (node (ref "J2") (pin "15") (pinfunction "GND1_15") (pintype "bidirectional"))
      (node (ref "J3") (pin "1") (pinfunction "GND_1") (pintype "bidirectional"))
      (node (ref "J3") (pin "14") (pinfunction "GND_14") (pintype "bidirectional"))
      (node (ref "J4") (pin "5") (pinfunction "GND_5") (pintype "bidirectional"))
      (node (ref "R1") (pin "1") (pinfunction "1_1") (pintype "passive"))
      (node (ref "R18") (pin "2") (pinfunction "2_2") (pintype "passive"))
      (node (ref "R20") (pin "2") (pinfunction "2_2") (pintype "passive"))
      (node (ref "R21") (pin "2") (pinfunction "2_2") (pintype "passive"))
      (node (ref "R24") (pin "2") (pinfunction "2_2") (pintype "passive"))
      (node (ref "R30") (pin "2") (pinfunction "2_2") (pintype "passive"))
      (node (ref "R31") (pin "2") (pinfunction "2_2") (pintype "passive"))
      (node (ref "R34") (pin "1") (pinfunction "1_1") (pintype "passive"))
      (node (ref "S1") (pin "1") (pinfunction "P$1_1") (pintype "passive"))
      (node (ref "U1") (pin "P7") (pinfunction "GND_P7") (pintype "bidirectional"))
      (node (ref "U10") (pin "15") (pinfunction "PGND_15") (pintype "bidirectional"))
      (node (ref "U10") (pin "16") (pinfunction "PGND_16") (pintype "bidirectional"))
      (node (ref "U10") (pin "6") (pinfunction "AGND_6") (pintype "bidirectional"))
      (node (ref "U10") (pin "7") (pinfunction "FSW_7") (pintype "bidirectional"))
      (node (ref "U10") (pin "8") (pinfunction "DEF_8") (pintype "bidirectional"))
      (node (ref "U10") (pin "GND") (pinfunction "PGND_GND") (pintype "bidirectional"))
      (node (ref "U2") (pin "3") (pinfunction "GND_3") (pintype "bidirectional"))
      (node (ref "U3") (pin "2") (pinfunction "VSS_2") (pintype "bidirectional"))
      (node (ref "U4") (pin "2") (pinfunction "VSS_2") (pintype "bidirectional"))
      (node (ref "U5") (pin "2") (pinfunction "V-_2") (pintype "power_in"))
      (node (ref "U6") (pin "2") (pinfunction "V-_2") (pintype "power_in"))
      (node (ref "U7") (pin "2") (pinfunction "V-_2") (pintype "power_in"))
      (node (ref "U8") (pin "2") (pinfunction "V-_2") (pintype "power_in"))
      (node (ref "U9") (pin "23") (pinfunction "GNDANA_23") (pintype "power_in"))
      (node (ref "U9") (pin "38") (pinfunction "GND_38") (pintype "power_in"))
      (node (ref "U9") (pin "6") (pinfunction "GND_6") (pintype "power_in"))
      (node (ref "U9") (pin "64") (pinfunction "GND_64") (pintype "power_in"))
      (node (ref "U9") (pin "GND") (pinfunction "GND_GND") (pintype "power_in"))
      (node (ref "X1") (pin "2") (pinfunction "GND_2") (pintype "bidirectional"))
      (node (ref "X1") (pin "4") (pinfunction "GND_4") (pintype "bidirectional"))
    )
    (net (code "15") (name "LEDG1") (class "Default")
      (node (ref "R2") (pin "1") (pinfunction "1_1") (pintype "passive"))
      (node (ref "U9") (pin "27") (pinfunction "PB06_27") (pintype "bidirectional"))
    )
    (net (code "16") (name "LEDG2") (class "Default")
      (node (ref "R4") (pin "1") (pinfunction "1_1") (pintype "passive"))
      (node (ref "U9") (pin "19") (pinfunction "PB04_19") (pintype "bidirectional"))
    )
    (net (code "17") (name "LEDR1") (class "Default")
      (node (ref "R3") (pin "1") (pinfunction "1_1") (pintype "passive"))
      (node (ref "U9") (pin "28") (pinfunction "PB07_28") (pintype "bidirectional"))
    )
    (net (code "18") (name "LEDR2") (class "Default")
      (node (ref "R5") (pin "1") (pinfunction "1_1") (pintype "passive"))
      (node (ref "U9") (pin "20") (pinfunction "PB05_20") (pintype "bidirectional"))
    )
    (net (code "19") (name "MOD_IN") (class "Default")
      (node (ref "J3") (pin "10") (pinfunction "MOD_IN_10") (pintype "bidirectional"))
      (node (ref "U9") (pin "51") (pinfunction "PA20_51") (pintype "bidirectional"))
    )
    (net (code "20") (name "MOD_OUT") (class "Default")
      (node (ref "J3") (pin "8") (pinfunction "MOD_OUT_8") (pintype "bidirectional"))
      (node (ref "U9") (pin "50") (pinfunction "PA19_50") (pintype "bidirectional"))
    )
    (net (code "21") (name "Net-(C30-Pad1)") (class "Default")
      (node (ref "C30") (pin "1") (pinfunction "1_1") (pintype "bidirectional"))
      (node (ref "R6") (pin "1") (pinfunction "1_1") (pintype "passive"))
    )
    (net (code "22") (name "Net-(C30-Pad2)") (class "Default")
      (node (ref "C30") (pin "2") (pinfunction "2_2") (pintype "bidirectional"))
      (node (ref "C7") (pin "1") (pinfunction "1_1") (pintype "bidirectional"))
      (node (ref "R13") (pin "2") (pinfunction "2_2") (pintype "passive"))
    )
    (net (code "23") (name "Net-(C31-Pad1)") (class "Default")
      (node (ref "C31") (pin "1") (pinfunction "1_1") (pintype "bidirectional"))
      (node (ref "R7") (pin "1") (pinfunction "1_1") (pintype "passive"))
    )
    (net (code "24") (name "Net-(C31-Pad2)") (class "Default")
      (node (ref "C31") (pin "2") (pinfunction "2_2") (pintype "bidirectional"))
      (node (ref "C8") (pin "1") (pinfunction "1_1") (pintype "bidirectional"))
      (node (ref "R14") (pin "2") (pinfunction "2_2") (pintype "passive"))
    )
    (net (code "25") (name "Net-(FB1-P$1)") (class "Default")
      (node (ref "C21") (pin "1") (pinfunction "1_1") (pintype "bidirectional"))
      (node (ref "FB1") (pin "1") (pinfunction "P$1_1") (pintype "bidirectional"))
      (node (ref "U9") (pin "24") (pinfunction "ADVREFP_24") (pintype "bidirectional"))
      (node (ref "U9") (pin "25") (pinfunction "VDDANA_25") (pintype "power_in"))
    )
    (net (code "26") (name "Net-(J1-L)") (class "Default")
      (node (ref "J1") (pin "4") (pinfunction "L_4") (pintype "bidirectional"))
      (node (ref "R11") (pin "1") (pinfunction "1_1") (pintype "passive"))
    )
    (net (code "27") (name "Net-(J1-R)") (class "Default")
      (node (ref "J1") (pin "1") (pinfunction "R_1") (pintype "bidirectional"))
      (node (ref "R12") (pin "1") (pinfunction "1_1") (pintype "passive"))
    )
    (net (code "28") (name "Net-(J2-DBG_GPIO1)") (class "Default")
      (node (ref "J2") (pin "16") (pinfunction "DBG_GPIO1_16") (pintype "bidirectional"))
      (node (ref "U9") (pin "57") (pinfunction "PB14_57") (pintype "bidirectional"))
    )
    (net (code "29") (name "Net-(J2-DBG_GPIO2)") (class "Default")
      (node (ref "J2") (pin "19") (pinfunction "DBG_GPIO2_19") (pintype "bidirectional"))
      (node (ref "U9") (pin "58") (pinfunction "PB15_58") (pintype "bidirectional"))
    )
    (net (code "30") (name "Net-(L1-1)") (class "Default")
      (node (ref "L1") (pin "P$1") (pinfunction "1_P$1") (pintype "bidirectional"))
      (node (ref "U10") (pin "1") (pinfunction "SW_1") (pintype "bidirectional"))
      (node (ref "U10") (pin "2") (pinfunction "SW_2") (pintype "bidirectional"))
      (node (ref "U10") (pin "3") (pinfunction "SW_3") (pintype "bidirectional"))
    )
    (net (code "31") (name "Net-(L2-1)") (class "Default")
      (node (ref "L2") (pin "P$1") (pinfunction "1_P$1") (pintype "bidirectional"))
      (node (ref "U9") (pin "7") (pinfunction "VDDOUT_7") (pintype "power_in"))
    )
    (net (code "32") (name "Net-(L2-2)") (class "Default")
      (node (ref "C20") (pin "1") (pinfunction "1_1") (pintype "bidirectional"))
      (node (ref "C32") (pin "1") (pinfunction "1_1") (pintype "bidirectional"))
      (node (ref "L2") (pin "P$2") (pinfunction "2_P$2") (pintype "bidirectional"))
      (node (ref "U9") (pin "5") (pinfunction "VDDCORE_5") (pintype "power_in"))
    )
    (net (code "33") (name "Net-(LED1-CATHODE)") (class "Default")
      (node (ref "LED1") (pin "C") (pinfunction "CATHODE_C") (pintype "bidirectional"))
      (node (ref "R2") (pin "2") (pinfunction "2_2") (pintype "passive"))
    )
    (net (code "34") (name "Net-(LED2-CATHODE)") (class "Default")
      (node (ref "LED2") (pin "C") (pinfunction "CATHODE_C") (pintype "bidirectional"))
      (node (ref "R3") (pin "2") (pinfunction "2_2") (pintype "passive"))
    )
    (net (code "35") (name "Net-(LED3-CATHODE)") (class "Default")
      (node (ref "LED3") (pin "C") (pinfunction "CATHODE_C") (pintype "bidirectional"))
      (node (ref "R4") (pin "2") (pinfunction "2_2") (pintype "passive"))
    )
    (net (code "36") (name "Net-(LED4-CATHODE)") (class "Default")
      (node (ref "LED4") (pin "C") (pinfunction "CATHODE_C") (pintype "bidirectional"))
      (node (ref "R5") (pin "2") (pinfunction "2_2") (pintype "passive"))
    )
    (net (code "37") (name "Net-(P1-CW)") (class "Default")
      (node (ref "C5") (pin "2") (pinfunction "2_2") (pintype "bidirectional"))
      (node (ref "P1") (pin "2") (pinfunction "CW_2") (pintype "bidirectional"))
      (node (ref "R25") (pin "1") (pinfunction "1_1") (pintype "passive"))
      (node (ref "R6") (pin "2") (pinfunction "2_2") (pintype "passive"))
      (node (ref "U5") (pin "4") (pinfunction "-IN_4") (pintype "input"))
    )
    (net (code "38") (name "Net-(P1-W)") (class "Default")
      (node (ref "C10") (pin "2") (pinfunction "2_2") (pintype "bidirectional"))
      (node (ref "C5") (pin "1") (pinfunction "1_1") (pintype "bidirectional"))
      (node (ref "P1") (pin "3") (pinfunction "W_3") (pintype "bidirectional"))
      (node (ref "R25") (pin "2") (pinfunction "2_2") (pintype "passive"))
      (node (ref "R8") (pin "1") (pinfunction "1_1") (pintype "passive"))
      (node (ref "TP9") (pin "TESTPOINT") (pinfunction "TESTPOINT_TESTPOINT") (pintype "bidirectional"))
      (node (ref "U5") (pin "1") (pinfunction "OUT_1") (pintype "output"))
    )
    (net (code "39") (name "Net-(P2-CW)") (class "Default")
      (node (ref "C6") (pin "2") (pinfunction "2_2") (pintype "bidirectional"))
      (node (ref "P2") (pin "2") (pinfunction "CW_2") (pintype "bidirectional"))
      (node (ref "R28") (pin "1") (pinfunction "1_1") (pintype "passive"))
      (node (ref "R7") (pin "2") (pinfunction "2_2") (pintype "passive"))
      (node (ref "U6") (pin "4") (pinfunction "-IN_4") (pintype "input"))
    )
    (net (code "40") (name "Net-(P2-W)") (class "Default")
      (node (ref "C6") (pin "1") (pinfunction "1_1") (pintype "bidirectional"))
      (node (ref "C9") (pin "2") (pinfunction "2_2") (pintype "bidirectional"))
      (node (ref "P2") (pin "3") (pinfunction "W_3") (pintype "bidirectional"))
      (node (ref "R28") (pin "2") (pinfunction "2_2") (pintype "passive"))
      (node (ref "R9") (pin "1") (pinfunction "1_1") (pintype "passive"))
      (node (ref "TP10") (pin "TESTPOINT") (pinfunction "TESTPOINT_TESTPOINT") (pintype "bidirectional"))
      (node (ref "U6") (pin "1") (pinfunction "OUT_1") (pintype "output"))
    )
    (net (code "41") (name "Net-(R11-Pad2)") (class "Default")
      (node (ref "R11") (pin "2") (pinfunction "2_2") (pintype "passive"))
      (node (ref "R12") (pin "2") (pinfunction "2_2") (pintype "passive"))
      (node (ref "R14") (pin "1") (pinfunction "1_1") (pintype "passive"))
    )
    (net (code "42") (name "Net-(U2-OUT)") (class "Default")
      (node (ref "R13") (pin "1") (pinfunction "1_1") (pintype "passive"))
      (node (ref "U2") (pin "1") (pinfunction "OUT_1") (pintype "bidirectional"))
    )
    (net (code "43") (name "Net-(U3-CLK)") (class "Default")
      (node (ref "C3") (pin "1") (pinfunction "1_1") (pintype "bidirectional"))
      (node (ref "R32") (pin "2") (pinfunction "2_2") (pintype "passive"))
      (node (ref "U3") (pin "8") (pinfunction "CLK_8") (pintype "bidirectional"))
    )
    (net (code "44") (name "Net-(U3-GND)") (class "Default")
      (node (ref "C15") (pin "1") (pinfunction "1_1") (pintype "bidirectional"))
      (node (ref "U3") (pin "6") (pinfunction "GND_6") (pintype "bidirectional"))
    )
    (net (code "45") (name "Net-(U3-IN)") (class "Default")
      (node (ref "C9") (pin "1") (pinfunction "1_1") (pintype "bidirectional"))
      (node (ref "U3") (pin "5") (pinfunction "IN_5") (pintype "bidirectional"))
    )
    (net (code "46") (name "Net-(U4-CLK)") (class "Default")
      (node (ref "C4") (pin "1") (pinfunction "1_1") (pintype "bidirectional"))
      (node (ref "R33") (pin "2") (pinfunction "2_2") (pintype "passive"))
      (node (ref "U4") (pin "8") (pinfunction "CLK_8") (pintype "bidirectional"))
    )
    (net (code "47") (name "Net-(U4-GND)") (class "Default")
      (node (ref "C17") (pin "1") (pinfunction "1_1") (pintype "bidirectional"))
      (node (ref "U4") (pin "6") (pinfunction "GND_6") (pintype "bidirectional"))
    )
    (net (code "48") (name "Net-(U4-IN)") (class "Default")
      (node (ref "C10") (pin "1") (pinfunction "1_1") (pintype "bidirectional"))
      (node (ref "U4") (pin "5") (pinfunction "IN_5") (pintype "bidirectional"))
    )
    (net (code "49") (name "Net-(U5-+IN)") (class "Default")
      (node (ref "C25") (pin "2") (pinfunction "2_2") (pintype "bidirectional"))
      (node (ref "R17") (pin "2") (pinfunction "2_2") (pintype "passive"))
      (node (ref "R18") (pin "1") (pinfunction "1_1") (pintype "passive"))
      (node (ref "U5") (pin "3") (pinfunction "+IN_3") (pintype "input"))
    )
    (net (code "50") (name "Net-(U6-+IN)") (class "Default")
      (node (ref "C26") (pin "2") (pinfunction "2_2") (pintype "bidirectional"))
      (node (ref "R19") (pin "2") (pinfunction "2_2") (pintype "passive"))
      (node (ref "R20") (pin "1") (pinfunction "1_1") (pintype "passive"))
      (node (ref "U6") (pin "3") (pinfunction "+IN_3") (pintype "input"))
    )
    (net (code "51") (name "Net-(U7-+IN)") (class "Default")
      (node (ref "C28") (pin "2") (pinfunction "2_2") (pintype "bidirectional"))
      (node (ref "R21") (pin "1") (pinfunction "1_1") (pintype "passive"))
      (node (ref "R22") (pin "2") (pinfunction "2_2") (pintype "passive"))
      (node (ref "U7") (pin "3") (pinfunction "+IN_3") (pintype "input"))
    )
    (net (code "52") (name "Net-(U7--IN)") (class "Default")
      (node (ref "C12") (pin "2") (pinfunction "2_2") (pintype "bidirectional"))
      (node (ref "R15") (pin "1") (pinfunction "1_1") (pintype "passive"))
      (node (ref "R8") (pin "2") (pinfunction "2_2") (pintype "passive"))
      (node (ref "U7") (pin "4") (pinfunction "-IN_4") (pintype "input"))
    )
    (net (code "53") (name "Net-(U8-+IN)") (class "Default")
      (node (ref "C29") (pin "2") (pinfunction "2_2") (pintype "bidirectional"))
      (node (ref "R23") (pin "2") (pinfunction "2_2") (pintype "passive"))
      (node (ref "R24") (pin "1") (pinfunction "1_1") (pintype "passive"))
      (node (ref "U8") (pin "3") (pinfunction "+IN_3") (pintype "input"))
    )
    (net (code "54") (name "Net-(U8--IN)") (class "Default")
      (node (ref "C13") (pin "2") (pinfunction "2_2") (pintype "bidirectional"))
      (node (ref "R16") (pin "1") (pinfunction "1_1") (pintype "passive"))
      (node (ref "R9") (pin "2") (pinfunction "2_2") (pintype "passive"))
      (node (ref "U8") (pin "4") (pinfunction "-IN_4") (pintype "input"))
    )
    (net (code "55") (name "Net-(U9-BIASH)") (class "Default")
      (node (ref "U9") (pin "36") (pinfunction "BIASH_36") (pintype "bidirectional"))
      (node (ref "U9") (pin "37") (pinfunction "BIASL_37") (pintype "bidirectional"))
    )
    (net (code "56") (name "Net-(U9-CAPH)") (class "Default")
      (node (ref "U9") (pin "33") (pinfunction "CAPH_33") (pintype "bidirectional"))
      (node (ref "U9") (pin "34") (pinfunction "CAPL_34") (pintype "bidirectional"))
    )
    (net (code "57") (name "Net-(U9-PA02)") (class "Default")
      (node (ref "R1") (pin "2") (pinfunction "2_2") (pintype "passive"))
      (node (ref "R10") (pin "1") (pinfunction "1_1") (pintype "passive"))
      (node (ref "U9") (pin "3") (pinfunction "PA02_3") (pintype "bidirectional"))
    )
    (net (code "58") (name "Net-(U9-PB01)") (class "Default")
      (node (ref "TP8") (pin "TESTPOINT") (pinfunction "TESTPOINT_TESTPOINT") (pintype "bidirectional"))
      (node (ref "U9") (pin "12") (pinfunction "PB01_12") (pintype "bidirectional"))
    )
    (net (code "59") (name "Net-(U10-FB)") (class "Default")
      (node (ref "R34") (pin "2") (pinfunction "2_2") (pintype "passive"))
      (node (ref "R35") (pin "1") (pinfunction "1_1") (pintype "passive"))
      (node (ref "U10") (pin "5") (pinfunction "FB_5") (pintype "bidirectional"))
    )
    (net (code "60") (name "Net-(U10-PG)") (class "Default")
      (node (ref "R29") (pin "1") (pinfunction "1_1") (pintype "passive"))
      (node (ref "U10") (pin "4") (pinfunction "PG_4") (pintype "bidirectional"))
    )
    (net (code "61") (name "Net-(U10-SS{slash}TR)") (class "Default")
      (node (ref "C14") (pin "2") (pinfunction "2_2") (pintype "bidirectional"))
      (node (ref "U10") (pin "9") (pinfunction "SS/TR_9") (pintype "bidirectional"))
    )
    (net (code "62") (name "PPS") (class "Default")
      (node (ref "J3") (pin "7") (pinfunction "PPS_7") (pintype "bidirectional"))
      (node (ref "U9") (pin "49") (pinfunction "PA18_49") (pintype "bidirectional"))
    )
    (net (code "63") (name "SCL") (class "Default")
      (node (ref "J3") (pin "5") (pinfunction "SCL_5") (pintype "bidirectional"))
      (node (ref "U9") (pin "60") (pinfunction "PA24_60") (pintype "bidirectional"))
    )
    (net (code "64") (name "SDA") (class "Default")
      (node (ref "J3") (pin "6") (pinfunction "SDA_6") (pintype "bidirectional"))
      (node (ref "U9") (pin "59") (pinfunction "PA23_59") (pintype "bidirectional"))
    )
    (net (code "65") (name "SPEC2_GATED") (class "Default")
      (node (ref "C16") (pin "1") (pinfunction "1_1") (pintype "bidirectional"))
      (node (ref "Q1") (pin "3") (pinfunction "D_3") (pintype "passive"))
      (node (ref "R19") (pin "1") (pinfunction "1_1") (pintype "passive"))
      (node (ref "R23") (pin "1") (pinfunction "1_1") (pintype "passive"))
      (node (ref "R32") (pin "1") (pinfunction "1_1") (pintype "passive"))
      (node (ref "U3") (pin "1") (pinfunction "VDD_1") (pintype "bidirectional"))
      (node (ref "U6") (pin "5") (pinfunction "V+_5") (pintype "power_in"))
      (node (ref "U8") (pin "5") (pinfunction "V+_5") (pintype "power_in"))
    )
    (net (code "66") (name "SPEC2_OUT") (class "Default")
      (node (ref "TP2") (pin "TESTPOINT") (pinfunction "TESTPOINT_TESTPOINT") (pintype "bidirectional"))
      (node (ref "U3") (pin "3") (pinfunction "OUT_3") (pintype "bidirectional"))
      (node (ref "U9") (pin "16") (pinfunction "PA05_16") (pintype "bidirectional"))
    )
    (net (code "67") (name "SPEC2_POWER") (class "Default")
      (node (ref "Q1") (pin "1") (pinfunction "G_1") (pintype "passive"))
      (node (ref "R30") (pin "1") (pinfunction "1_1") (pintype "passive"))
      (node (ref "TP4") (pin "TESTPOINT") (pinfunction "TESTPOINT_TESTPOINT") (pintype "bidirectional"))
      (node (ref "U9") (pin "26") (pinfunction "PA08_26") (pintype "bidirectional"))
    )
    (net (code "68") (name "SPEC2_RESET") (class "Default")
      (node (ref "TP3") (pin "TESTPOINT") (pinfunction "TESTPOINT_TESTPOINT") (pintype "bidirectional"))
      (node (ref "U3") (pin "7") (pinfunction "RESET_7") (pintype "bidirectional"))
      (node (ref "U9") (pin "22") (pinfunction "PA07_22") (pintype "bidirectional"))
    )
    (net (code "69") (name "SPEC2_STROBE") (class "Default")
      (node (ref "TP5") (pin "TESTPOINT") (pinfunction "TESTPOINT_TESTPOINT") (pintype "bidirectional"))
      (node (ref "U3") (pin "4") (pinfunction "STROBE_4") (pintype "bidirectional"))
      (node (ref "U9") (pin "21") (pinfunction "PA06_21") (pintype "bidirectional"))
    )
    (net (code "70") (name "SPEC_GATED") (class "Default")
      (node (ref "C11") (pin "2") (pinfunction "2_2") (pintype "bidirectional"))
      (node (ref "C18") (pin "1") (pinfunction "1_1") (pintype "bidirectional"))
      (node (ref "C27") (pin "2") (pinfunction "2_2") (pintype "bidirectional"))
      (node (ref "Q2") (pin "3") (pinfunction "D_3") (pintype "passive"))
      (node (ref "R17") (pin "1") (pinfunction "1_1") (pintype "passive"))
      (node (ref "R22") (pin "1") (pinfunction "1_1") (pintype "passive"))
      (node (ref "R33") (pin "1") (pinfunction "1_1") (pintype "passive"))
      (node (ref "U2") (pin "2") (pinfunction "VDD_2") (pintype "bidirectional"))
      (node (ref "U4") (pin "1") (pinfunction "VDD_1") (pintype "bidirectional"))
      (node (ref "U5") (pin "5") (pinfunction "V+_5") (pintype "power_in"))
      (node (ref "U7") (pin "5") (pinfunction "V+_5") (pintype "power_in"))
    )
    (net (code "71") (name "SPEC_OUT") (class "Default")
      (node (ref "TP1") (pin "TESTPOINT") (pinfunction "TESTPOINT_TESTPOINT") (pintype "bidirectional"))
      (node (ref "U4") (pin "3") (pinfunction "OUT_3") (pintype "bidirectional"))
      (node (ref "U9") (pin "15") (pinfunction "PA04_15") (pintype "bidirectional"))
    )
    (net (code "72") (name "SPEC_POWER") (class "Default")
      (node (ref "Q2") (pin "1") (pinfunction "G_1") (pintype "passive"))
      (node (ref "R31") (pin "1") (pinfunction "1_1") (pintype "passive"))
    )
    (net (code "73") (name "SPEC_RESET") (class "Default")
      (node (ref "TP7") (pin "TESTPOINT") (pinfunction "TESTPOINT_TESTPOINT") (pintype "bidirectional"))
      (node (ref "U4") (pin "7") (pinfunction "RESET_7") (pintype "bidirectional"))
      (node (ref "U9") (pin "11") (pinfunction "PB00_11") (pintype "bidirectional"))
    )
    (net (code "74") (name "SPEC_STROBE") (class "Default")
      (node (ref "TP6") (pin "TESTPOINT") (pinfunction "TESTPOINT_TESTPOINT") (pintype "bidirectional"))
      (node (ref "U4") (pin "4") (pinfunction "STROBE_4") (pintype "bidirectional"))
      (node (ref "U9") (pin "30") (pinfunction "PA10_30") (pintype "bidirectional"))
    )
    (net (code "75") (name "USB+") (class "Default")
      (node (ref "J3") (pin "11") (pinfunction "USB_D+_11") (pintype "bidirectional"))
      (node (ref "U9") (pin "63") (pinfunction "PA26_63") (pintype "bidirectional"))
    )
    (net (code "76") (name "USB-") (class "Default")
      (node (ref "J3") (pin "12") (pinfunction "USB_D-_12") (pintype "bidirectional"))
      (node (ref "U9") (pin "62") (pinfunction "PA25_62") (pintype "bidirectional"))
    )
    (net (code "77") (name "unconnected-(J1-LDET-Pad3)") (class "Default")
      (node (ref "J1") (pin "3") (pinfunction "LDET_3") (pintype "bidirectional"))
    )
    (net (code "78") (name "unconnected-(J1-RDET-Pad2)") (class "Default")
      (node (ref "J1") (pin "2") (pinfunction "RDET_2") (pintype "bidirectional"))
    )
    (net (code "79") (name "unconnected-(J3-USB_VBUS-Pad13)") (class "Default")
      (node (ref "J3") (pin "13") (pinfunction "USB_VBUS_13") (pintype "bidirectional"))
    )
    (net (code "80") (name "unconnected-(J4-SWO-Pad6)") (class "Default")
      (node (ref "J4") (pin "6") (pinfunction "SWO_6") (pintype "bidirectional"))
    )
    (net (code "81") (name "unconnected-(P1-CCW-Pad1)") (class "Default")
      (node (ref "P1") (pin "1") (pinfunction "CCW_1") (pintype "bidirectional"))
    )
    (net (code "82") (name "unconnected-(P2-CCW-Pad1)") (class "Default")
      (node (ref "P2") (pin "1") (pinfunction "CCW_1") (pintype "bidirectional"))
    )
    (net (code "83") (name "unconnected-(U9-PA09-Pad29)") (class "Default")
      (node (ref "U9") (pin "29") (pinfunction "PA09_29") (pintype "bidirectional"))
    )
    (net (code "84") (name "unconnected-(U9-PA13-Pad40)") (class "Default")
      (node (ref "U9") (pin "40") (pinfunction "PA13_40") (pintype "bidirectional"))
    )
    (net (code "85") (name "unconnected-(U9-PA14-Pad41)") (class "Default")
      (node (ref "U9") (pin "41") (pinfunction "PA14_41") (pintype "bidirectional"))
    )
    (net (code "86") (name "unconnected-(U9-PA16-Pad43)") (class "Default")
      (node (ref "U9") (pin "43") (pinfunction "PA16_43") (pintype "bidirectional"))
    )
    (net (code "87") (name "unconnected-(U9-PA17-Pad44)") (class "Default")
      (node (ref "U9") (pin "44") (pinfunction "PA17_44") (pintype "bidirectional"))
    )
    (net (code "88") (name "unconnected-(U9-PA21-Pad55)") (class "Default")
      (node (ref "U9") (pin "55") (pinfunction "PA21_55") (pintype "bidirectional"))
    )
    (net (code "89") (name "unconnected-(U9-PA22-Pad56)") (class "Default")
      (node (ref "U9") (pin "56") (pinfunction "PA22_56") (pintype "bidirectional"))
    )
    (net (code "90") (name "unconnected-(U9-PB12-Pad53)") (class "Default")
      (node (ref "U9") (pin "53") (pinfunction "PB12_53") (pintype "bidirectional"))
    )
    (net (code "91") (name "unconnected-(U9-PB13-Pad54)") (class "Default")
      (node (ref "U9") (pin "54") (pinfunction "PB13_54") (pintype "bidirectional"))
    )
    (net (code "92") (name "unconnected-(U9-XIN32-Pad17)") (class "Default")
      (node (ref "U9") (pin "17") (pinfunction "XIN32_17") (pintype "bidirectional"))
    )
    (net (code "93") (name "unconnected-(U9-XOUT32-Pad18)") (class "Default")
      (node (ref "U9") (pin "18") (pinfunction "XOUT32_18") (pintype "bidirectional"))
    )
    (net (code "94") (name "~{AUDIO_RESET}") (class "Default")
      (node (ref "J2") (pin "20") (pinfunction "DBG_~{RESET}_20") (pintype "bidirectional"))
      (node (ref "J4") (pin "3") (pinfunction "~{RESET}_3") (pintype "bidirectional"))
      (node (ref "S1") (pin "2") (pinfunction "P$2_2") (pintype "passive"))
      (node (ref "U9") (pin "4") (pinfunction "~{RESET}_4") (pintype "bidirectional"))
    )
    (net (code "95") (name "~{FLASH_CS}") (class "Default")
      (node (ref "!CS") (pin "TESTPOINT") (pinfunction "TESTPOINT_TESTPOINT") (pintype "bidirectional"))
      (node (ref "U1") (pin "P4") (pinfunction "~{CS}_P4") (pintype "bidirectional"))
      (node (ref "U9") (pin "42") (pinfunction "PA15_42") (pintype "bidirectional"))
    )
    (net (code "96") (name "~{FLASH_RESET}") (class "Default")
      (node (ref "U1") (pin "P3") (pinfunction "~{RESET}_P3") (pintype "bidirectional"))
      (node (ref "U9") (pin "48") (pinfunction "PB11_48") (pintype "bidirectional"))
    )
  )
)
